# sensor-board.net
KiCad netlist of a schematic drawn in EAGLE
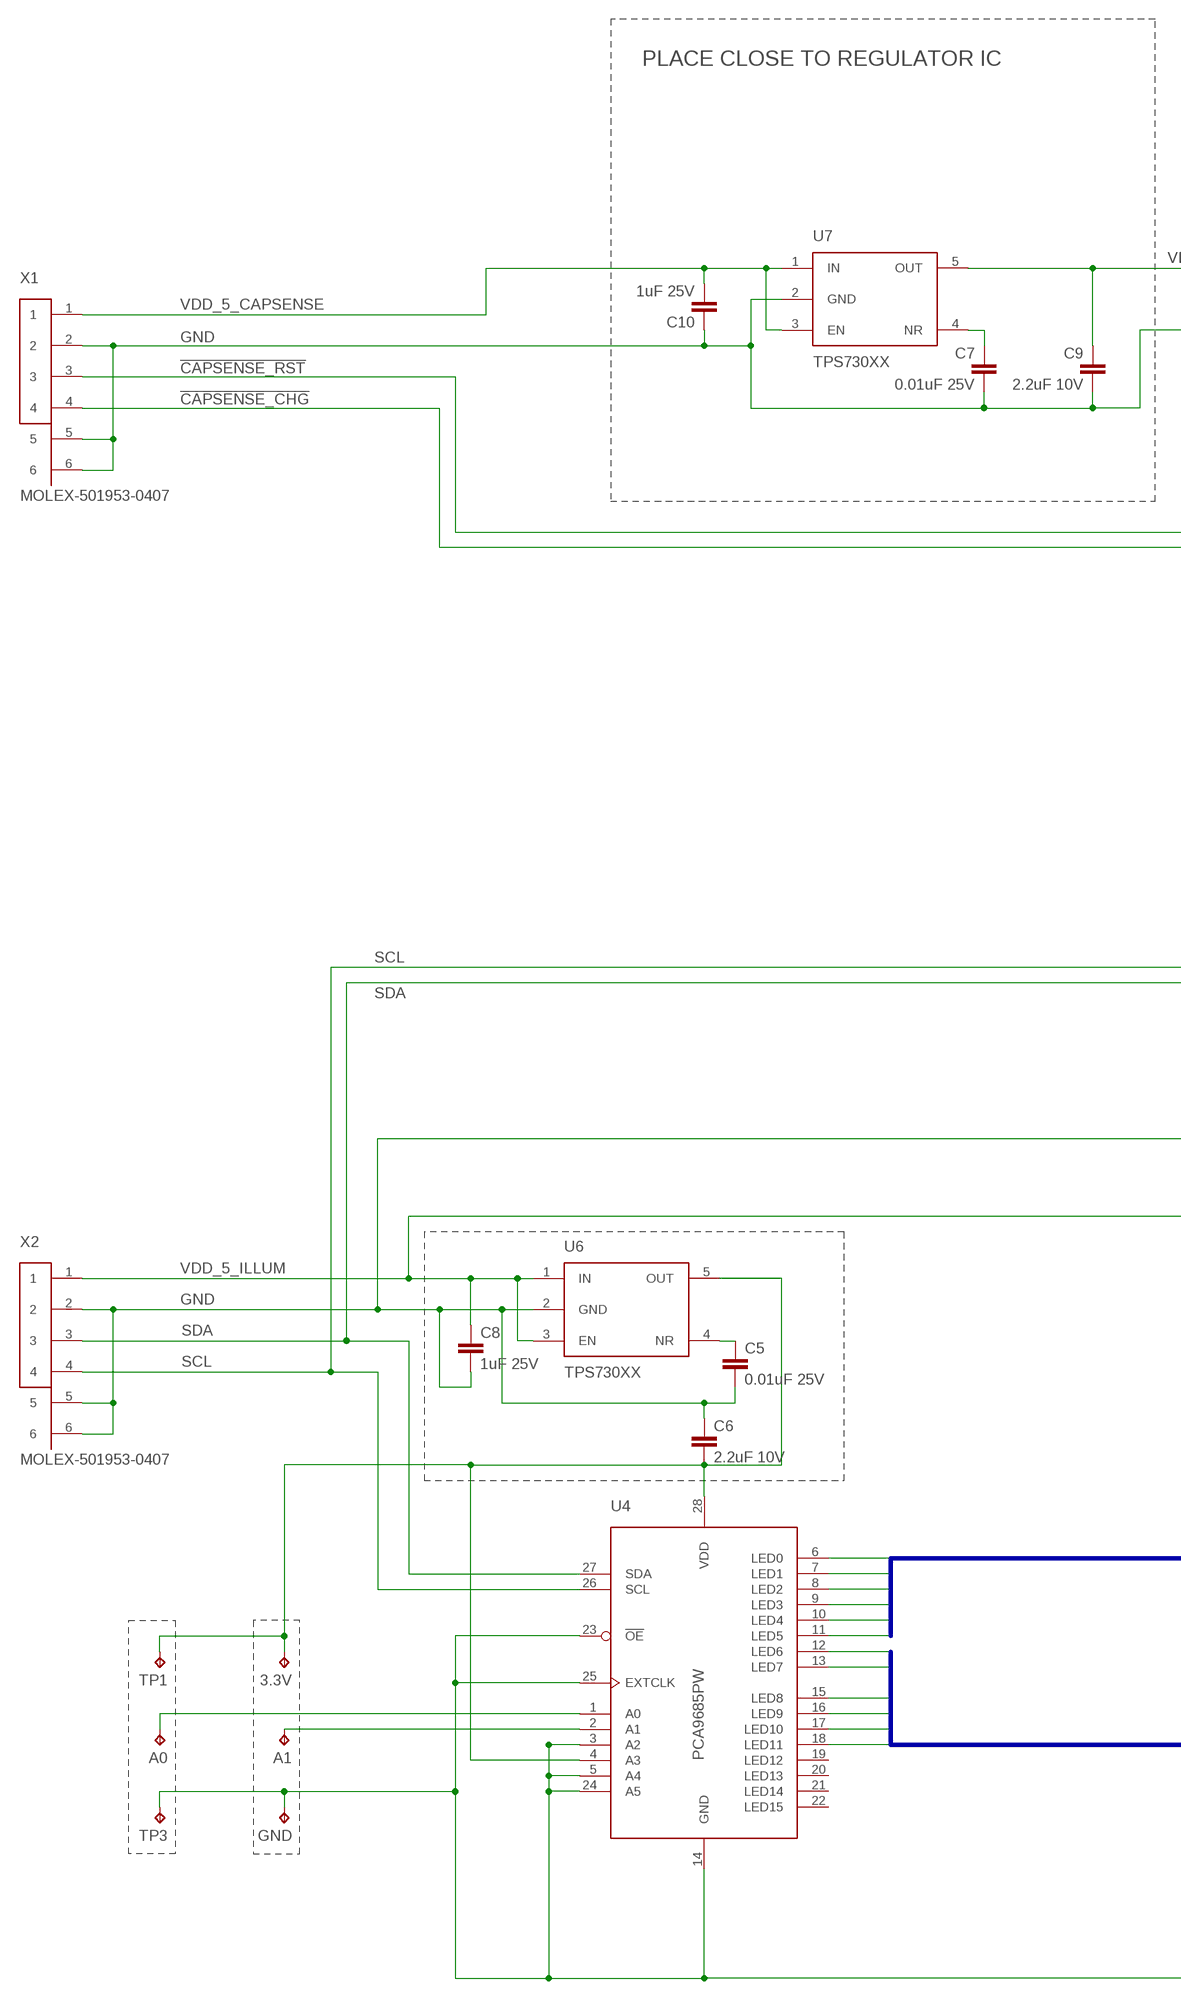
[diagram p0: schematic, sheet 1, part 1 of 2]
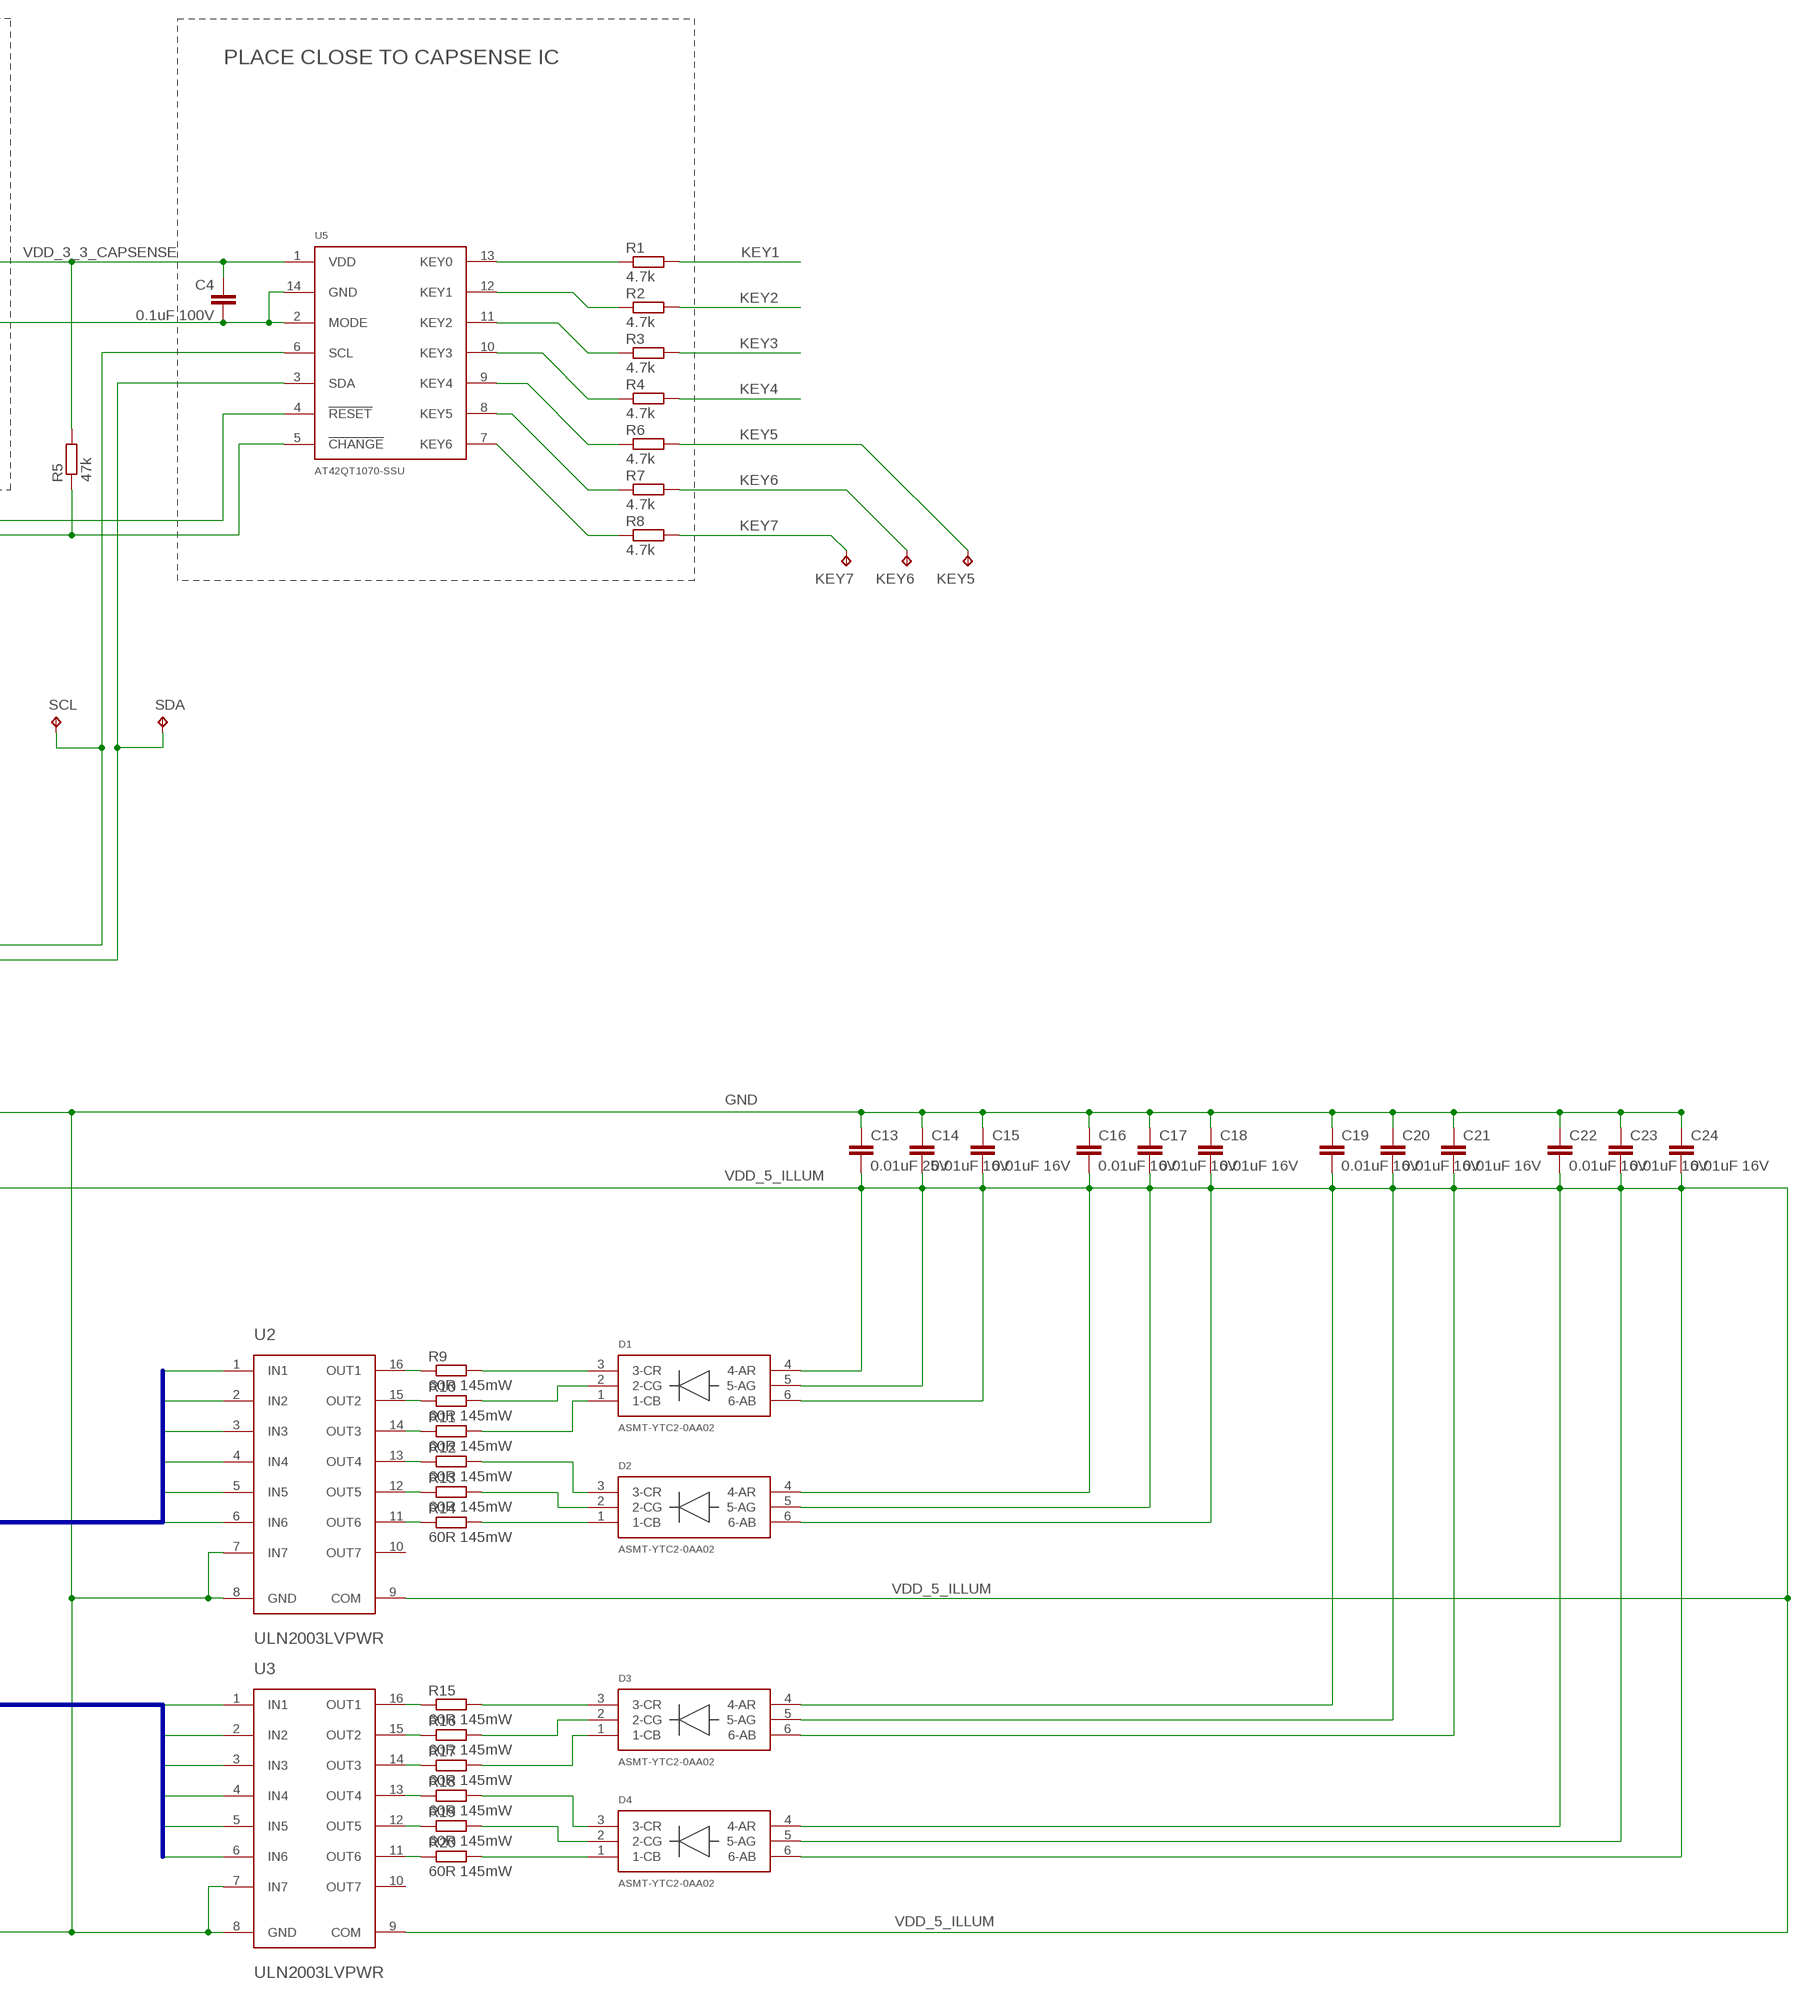
[diagram p1: schematic, sheet 1, part 2 of 2]

(export (version "E")
  (design (tool "Eeschema 10.0.6"))
  (components
    (comp (ref "3.3V")
      (value "TPB1,27")
      (footprint "eagle-import:B1,27")
      (libsource (lib "eagle-import") (part "TPB1,27"))
    )
    (comp (ref "A0")
      (value "TPB1,27")
      (footprint "eagle-import:B1,27")
      (libsource (lib "eagle-import") (part "TPB1,27"))
    )
    (comp (ref "A1")
      (value "TPB1,27")
      (footprint "eagle-import:B1,27")
      (libsource (lib "eagle-import") (part "TPB1,27"))
    )
    (comp (ref "C4")
      (value "0.1uF 100V")
      (footprint "eagle-import:C0402K")
      (fields (field (name "MFR_PART") "0402YC104KAT2A"))
      (libsource (lib "eagle-import") (part "C-EUC0402K"))
    )
    (comp (ref "C5")
      (value "0.01uF 25V")
      (footprint "eagle-import:C0402K")
      (fields (field (name "MFR_PART") "C0402C103J3RACTU"))
      (libsource (lib "eagle-import") (part "C-EUC0402K"))
    )
    (comp (ref "C6")
      (value "2.2uF 10V")
      (footprint "eagle-import:C0402K")
      (fields (field (name "MFR_PART") "C0402C225M8PAC TU "))
      (libsource (lib "eagle-import") (part "C-EUC0402K"))
    )
    (comp (ref "C7")
      (value "0.01uF 25V")
      (footprint "eagle-import:C0402K")
      (fields (field (name "MFR_PART") "C0402C103J3RACTU"))
      (libsource (lib "eagle-import") (part "C-EUC0402K"))
    )
    (comp (ref "C8")
      (value "1uF 25V")
      (footprint "eagle-import:C0402K")
      (fields (field (name "MFR_PART") "C1005X5R1A105K050BB"))
      (libsource (lib "eagle-import") (part "C-EUC0402K"))
    )
    (comp (ref "C9")
      (value "2.2uF 10V")
      (footprint "eagle-import:C0402K")
      (fields (field (name "MFR_PART") "C1608X7R1C105K080AC"))
      (libsource (lib "eagle-import") (part "C-EUC0402K"))
    )
    (comp (ref "C10")
      (value "1uF 25V")
      (footprint "eagle-import:C0402K")
      (fields (field (name "MFR_PART") "C1005X5R1A105K050BB"))
      (libsource (lib "eagle-import") (part "C-EUC0402K"))
    )
    (comp (ref "C13")
      (value "0.01uF 25V")
      (footprint "eagle-import:C0402K")
      (fields (field (name "MFR_PART") "C0402C103J3RACTU"))
      (libsource (lib "eagle-import") (part "C-EUC0402K"))
    )
    (comp (ref "C14")
      (value "0.01uF 16V")
      (footprint "eagle-import:C0402K")
      (fields (field (name "MFR_PART") "C0402C103J3RACTU"))
      (libsource (lib "eagle-import") (part "C-EUC0402K"))
    )
    (comp (ref "C15")
      (value "0.01uF 16V")
      (footprint "eagle-import:C0402K")
      (fields (field (name "MFR_PART") "C0402C103J3RACTU"))
      (libsource (lib "eagle-import") (part "C-EUC0402K"))
    )
    (comp (ref "C16")
      (value "0.01uF 16V")
      (footprint "eagle-import:C0402K")
      (fields (field (name "MFR_PART") "C0402C103J3RACTU"))
      (libsource (lib "eagle-import") (part "C-EUC0402K"))
    )
    (comp (ref "C17")
      (value "0.01uF 16V")
      (footprint "eagle-import:C0402K")
      (fields (field (name "MFR_PART") "C0402C103J3RACTU"))
      (libsource (lib "eagle-import") (part "C-EUC0402K"))
    )
    (comp (ref "C18")
      (value "0.01uF 16V")
      (footprint "eagle-import:C0402K")
      (fields (field (name "MFR_PART") "C0402C103J3RACTU"))
      (libsource (lib "eagle-import") (part "C-EUC0402K"))
    )
    (comp (ref "C19")
      (value "0.01uF 16V")
      (footprint "eagle-import:C0402K")
      (fields (field (name "MFR_PART") "C0402C103J3RACTU"))
      (libsource (lib "eagle-import") (part "C-EUC0402K"))
    )
    (comp (ref "C20")
      (value "0.01uF 16V")
      (footprint "eagle-import:C0402K")
      (fields (field (name "MFR_PART") "C0402C103J3RACTU"))
      (libsource (lib "eagle-import") (part "C-EUC0402K"))
    )
    (comp (ref "C21")
      (value "0.01uF 16V")
      (footprint "eagle-import:C0402K")
      (fields (field (name "MFR_PART") "C0402C103J3RACTU"))
      (libsource (lib "eagle-import") (part "C-EUC0402K"))
    )
    (comp (ref "C22")
      (value "0.01uF 16V")
      (footprint "eagle-import:C0402K")
      (fields (field (name "MFR_PART") "C0402C103J3RACTU"))
      (libsource (lib "eagle-import") (part "C-EUC0402K"))
    )
    (comp (ref "C23")
      (value "0.01uF 16V")
      (footprint "eagle-import:C0402K")
      (fields (field (name "MFR_PART") "C0402C103J3RACTU"))
      (libsource (lib "eagle-import") (part "C-EUC0402K"))
    )
    (comp (ref "C24")
      (value "0.01uF 16V")
      (footprint "eagle-import:C0402K")
      (fields (field (name "MFR_PART") "C0402C103J3RACTU"))
      (libsource (lib "eagle-import") (part "C-EUC0402K"))
    )
    (comp (ref "D1")
      (value "ASMT-YTC2-0AA02")
      (footprint "eagle-import:ASMT-YTC2-0AA02-REV")
      (libsource (lib "eagle-import") (part "ASMT-YTC2-0AA02"))
    )
    (comp (ref "D2")
      (value "ASMT-YTC2-0AA02")
      (footprint "eagle-import:ASMT-YTC2-0AA02-REV")
      (libsource (lib "eagle-import") (part "ASMT-YTC2-0AA02"))
    )
    (comp (ref "D3")
      (value "ASMT-YTC2-0AA02")
      (footprint "eagle-import:ASMT-YTC2-0AA02-REV")
      (libsource (lib "eagle-import") (part "ASMT-YTC2-0AA02"))
    )
    (comp (ref "D4")
      (value "ASMT-YTC2-0AA02")
      (footprint "eagle-import:ASMT-YTC2-0AA02-REV")
      (libsource (lib "eagle-import") (part "ASMT-YTC2-0AA02"))
    )
    (comp (ref "GND")
      (value "TPB1,27")
      (footprint "eagle-import:B1,27")
      (libsource (lib "eagle-import") (part "TPB1,27"))
    )
    (comp (ref "KEY5")
      (value "TPTP06R")
      (footprint "eagle-import:TP06R")
      (libsource (lib "eagle-import") (part "TPTP06R"))
    )
    (comp (ref "KEY6")
      (value "TPTP06R")
      (footprint "eagle-import:TP06R")
      (libsource (lib "eagle-import") (part "TPTP06R"))
    )
    (comp (ref "KEY7")
      (value "TPTP06R")
      (footprint "eagle-import:TP06R")
      (libsource (lib "eagle-import") (part "TPTP06R"))
    )
    (comp (ref "R1")
      (value "4.7k")
      (footprint "eagle-import:R0402")
      (fields (field (name "MFR_PART") "PCF0402PR-4K7BT1"))
      (libsource (lib "eagle-import") (part "R-EU_NKR0402"))
    )
    (comp (ref "R2")
      (value "4.7k")
      (footprint "eagle-import:R0402")
      (fields (field (name "MFR_PART") "PCF0402PR-4K7BT1 "))
      (libsource (lib "eagle-import") (part "R-EU_NKR0402"))
    )
    (comp (ref "R3")
      (value "4.7k")
      (footprint "eagle-import:R0402")
      (fields (field (name "MFR_PART") "PCF0402PR-4K7BT1 "))
      (libsource (lib "eagle-import") (part "R-EU_NKR0402"))
    )
    (comp (ref "R4")
      (value "4.7k")
      (footprint "eagle-import:R0402")
      (fields (field (name "MFR_PART") "PCF0402PR-4K7BT1 "))
      (libsource (lib "eagle-import") (part "R-EU_NKR0402"))
    )
    (comp (ref "R5")
      (value "47k")
      (footprint "eagle-import:R0402")
      (fields (field (name "MFR_PART") "RC0402JR-0747KL"))
      (libsource (lib "eagle-import") (part "R-EU_NKR0402"))
    )
    (comp (ref "R6")
      (value "4.7k")
      (footprint "eagle-import:R0402")
      (fields (field (name "MFR_PART") "PCF0402PR-4K7BT1 "))
      (libsource (lib "eagle-import") (part "R-EU_NKR0402"))
    )
    (comp (ref "R7")
      (value "4.7k")
      (footprint "eagle-import:R0402")
      (fields (field (name "MFR_PART") "PCF0402PR-4K7BT1 "))
      (libsource (lib "eagle-import") (part "R-EU_NKR0402"))
    )
    (comp (ref "R8")
      (value "4.7k")
      (footprint "eagle-import:R0402")
      (fields (field (name "MFR_PART") "PCF0402PR-4K7BT1 "))
      (libsource (lib "eagle-import") (part "R-EU_NKR0402"))
    )
    (comp (ref "R9")
      (value "60R 145mW")
      (footprint "eagle-import:R0603")
      (fields (field (name "MFR_PART") "ERJP03F62R0V"))
      (libsource (lib "eagle-import") (part "R-EU_NKR0603"))
    )
    (comp (ref "R10")
      (value "60R 145mW")
      (footprint "eagle-import:R0603")
      (fields (field (name "MFR_PART") "ERJP03F62R0V"))
      (libsource (lib "eagle-import") (part "R-EU_NKR0603"))
    )
    (comp (ref "R11")
      (value "60R 145mW")
      (footprint "eagle-import:R0603")
      (fields (field (name "MFR_PART") "ERJP03F62R0V"))
      (libsource (lib "eagle-import") (part "R-EU_NKR0603"))
    )
    (comp (ref "R12")
      (value "60R 145mW")
      (footprint "eagle-import:R0603")
      (fields (field (name "MFR_PART") "ERJP03F62R0V"))
      (libsource (lib "eagle-import") (part "R-EU_NKR0603"))
    )
    (comp (ref "R13")
      (value "60R 145mW")
      (footprint "eagle-import:R0603")
      (fields (field (name "MFR_PART") "ERJP03F62R0V"))
      (libsource (lib "eagle-import") (part "R-EU_NKR0603"))
    )
    (comp (ref "R14")
      (value "60R 145mW")
      (footprint "eagle-import:R0603")
      (fields (field (name "MFR_PART") "ERJP03F62R0V"))
      (libsource (lib "eagle-import") (part "R-EU_NKR0603"))
    )
    (comp (ref "R15")
      (value "60R 145mW")
      (footprint "eagle-import:R0603")
      (fields (field (name "MFR_PART") "ERJP03F62R0V"))
      (libsource (lib "eagle-import") (part "R-EU_NKR0603"))
    )
    (comp (ref "R16")
      (value "60R 145mW")
      (footprint "eagle-import:R0603")
      (fields (field (name "MFR_PART") "ERJP03F62R0V"))
      (libsource (lib "eagle-import") (part "R-EU_NKR0603"))
    )
    (comp (ref "R17")
      (value "60R 145mW")
      (footprint "eagle-import:R0603")
      (fields (field (name "MFR_PART") "ERJP03F62R0V"))
      (libsource (lib "eagle-import") (part "R-EU_NKR0603"))
    )
    (comp (ref "R18")
      (value "60R 145mW")
      (footprint "eagle-import:R0603")
      (fields (field (name "MFR_PART") "ERJP03F62R0V"))
      (libsource (lib "eagle-import") (part "R-EU_NKR0603"))
    )
    (comp (ref "R19")
      (value "60R 145mW")
      (footprint "eagle-import:R0603")
      (fields (field (name "MFR_PART") "ERJP03F62R0V"))
      (libsource (lib "eagle-import") (part "R-EU_NKR0603"))
    )
    (comp (ref "R20")
      (value "60R 145mW")
      (footprint "eagle-import:R0603")
      (fields (field (name "MFR_PART") "ERJP03F62R0V"))
      (libsource (lib "eagle-import") (part "R-EU_NKR0603"))
    )
    (comp (ref "SCL")
      (value "TPTP06R")
      (footprint "eagle-import:TP06R")
      (libsource (lib "eagle-import") (part "TPTP06R"))
    )
    (comp (ref "SDA")
      (value "TPTP06R")
      (footprint "eagle-import:TP06R")
      (libsource (lib "eagle-import") (part "TPTP06R"))
    )
    (comp (ref "TP1")
      (value "TPB1,27")
      (footprint "eagle-import:B1,27")
      (libsource (lib "eagle-import") (part "TPB1,27"))
    )
    (comp (ref "TP3")
      (value "TPB1,27")
      (footprint "eagle-import:B1,27")
      (libsource (lib "eagle-import") (part "TPB1,27"))
    )
    (comp (ref "U2")
      (value "ULN2003LVPWR")
      (footprint "eagle-import:TSSOP-PW-R-PDSO-G16")
      (libsource (lib "eagle-import") (part "ULN2003LVPWR"))
    )
    (comp (ref "U3")
      (value "ULN2003LVPWR")
      (footprint "eagle-import:TSSOP-PW-R-PDSO-G16")
      (libsource (lib "eagle-import") (part "ULN2003LVPWR"))
    )
    (comp (ref "U4")
      (value "PCA9685PW")
      (footprint "eagle-import:SOT361-1")
      (libsource (lib "eagle-import") (part "PCA9685PW"))
    )
    (comp (ref "U5")
      (value "AT42QT1070-SSU")
      (footprint "eagle-import:SO14")
      (libsource (lib "eagle-import") (part "AT42QT1070-SSU"))
    )
    (comp (ref "U6")
      (value "TPS730XX")
      (footprint "eagle-import:SOT23-5")
      (libsource (lib "eagle-import") (part "TPS730XX"))
    )
    (comp (ref "U7")
      (value "TPS730XX")
      (footprint "eagle-import:SOT23-5")
      (libsource (lib "eagle-import") (part "TPS730XX"))
    )
    (comp (ref "X1")
      (value "MOLEX-501953-0407")
      (footprint "eagle-import:MOLEX-501953-0407")
      (libsource (lib "eagle-import") (part "MOLEX-501953-0407"))
    )
    (comp (ref "X2")
      (value "MOLEX-501953-0407")
      (footprint "eagle-import:MOLEX-501953-0407")
      (libsource (lib "eagle-import") (part "MOLEX-501953-0407"))
    )
  )
  (nets
    (net (code "1") (name "/GND") (class "Default")
      (node (ref "C10") (pin "1") (pinfunction "1_1") (pintype "passive"))
      (node (ref "C13") (pin "1") (pinfunction "1_1") (pintype "passive"))
      (node (ref "C14") (pin "1") (pinfunction "1_1") (pintype "passive"))
      (node (ref "C15") (pin "1") (pinfunction "1_1") (pintype "passive"))
      (node (ref "C16") (pin "1") (pinfunction "1_1") (pintype "passive"))
      (node (ref "C17") (pin "1") (pinfunction "1_1") (pintype "passive"))
      (node (ref "C18") (pin "1") (pinfunction "1_1") (pintype "passive"))
      (node (ref "C19") (pin "1") (pinfunction "1_1") (pintype "passive"))
      (node (ref "C20") (pin "1") (pinfunction "1_1") (pintype "passive"))
      (node (ref "C21") (pin "1") (pinfunction "1_1") (pintype "passive"))
      (node (ref "C22") (pin "1") (pinfunction "1_1") (pintype "passive"))
      (node (ref "C23") (pin "1") (pinfunction "1_1") (pintype "passive"))
      (node (ref "C24") (pin "1") (pinfunction "1_1") (pintype "passive"))
      (node (ref "C4") (pin "2") (pinfunction "2_2") (pintype "passive"))
      (node (ref "C5") (pin "2") (pinfunction "2_2") (pintype "passive"))
      (node (ref "C6") (pin "1") (pinfunction "1_1") (pintype "passive"))
      (node (ref "C7") (pin "2") (pinfunction "2_2") (pintype "passive"))
      (node (ref "C8") (pin "2") (pinfunction "2_2") (pintype "passive"))
      (node (ref "C9") (pin "2") (pinfunction "2_2") (pintype "passive"))
      (node (ref "GND") (pin "TP") (pinfunction "TP_TP") (pintype "input"))
      (node (ref "TP3") (pin "TP") (pinfunction "TP_TP") (pintype "input"))
      (node (ref "U2") (pin "7") (pinfunction "IN7_7") (pintype "bidirectional"))
      (node (ref "U2") (pin "8") (pinfunction "GND_8") (pintype "power_in"))
      (node (ref "U3") (pin "7") (pinfunction "IN7_7") (pintype "bidirectional"))
      (node (ref "U3") (pin "8") (pinfunction "GND_8") (pintype "power_in"))
      (node (ref "U4") (pin "14") (pinfunction "GND_14") (pintype "power_in"))
      (node (ref "U4") (pin "23") (pinfunction "~{OE}_23") (pintype "bidirectional"))
      (node (ref "U4") (pin "24") (pinfunction "A5_24") (pintype "bidirectional"))
      (node (ref "U4") (pin "25") (pinfunction "EXTCLK_25") (pintype "input"))
      (node (ref "U4") (pin "3") (pinfunction "A2_3") (pintype "bidirectional"))
      (node (ref "U4") (pin "5") (pinfunction "A4_5") (pintype "bidirectional"))
      (node (ref "U5") (pin "14") (pinfunction "GND_14") (pintype "power_in"))
      (node (ref "U5") (pin "2") (pinfunction "MODE_2") (pintype "input"))
      (node (ref "U6") (pin "2") (pinfunction "GND_2") (pintype "power_in"))
      (node (ref "U7") (pin "2") (pinfunction "GND_2") (pintype "power_in"))
      (node (ref "X1") (pin "2") (pinfunction "2_2") (pintype "bidirectional"))
      (node (ref "X1") (pin "5") (pinfunction "5_5") (pintype "bidirectional"))
      (node (ref "X1") (pin "6") (pinfunction "6_6") (pintype "bidirectional"))
      (node (ref "X2") (pin "2") (pinfunction "2_2") (pintype "bidirectional"))
      (node (ref "X2") (pin "5") (pinfunction "5_5") (pintype "bidirectional"))
      (node (ref "X2") (pin "6") (pinfunction "6_6") (pintype "bidirectional"))
    )
    (net (code "2") (name "/KEY1") (class "Default")
      (node (ref "R1") (pin "2") (pinfunction "2_2") (pintype "passive"))
    )
    (net (code "3") (name "/KEY2") (class "Default")
      (node (ref "R2") (pin "2") (pinfunction "2_2") (pintype "passive"))
    )
    (net (code "4") (name "/KEY3") (class "Default")
      (node (ref "R3") (pin "2") (pinfunction "2_2") (pintype "passive"))
    )
    (net (code "5") (name "/KEY4") (class "Default")
      (node (ref "R4") (pin "2") (pinfunction "2_2") (pintype "passive"))
    )
    (net (code "6") (name "/KEY5") (class "Default")
      (node (ref "KEY5") (pin "TP") (pinfunction "TP_TP") (pintype "input"))
      (node (ref "R6") (pin "2") (pinfunction "2_2") (pintype "passive"))
    )
    (net (code "7") (name "/KEY6") (class "Default")
      (node (ref "KEY6") (pin "TP") (pinfunction "TP_TP") (pintype "input"))
      (node (ref "R7") (pin "2") (pinfunction "2_2") (pintype "passive"))
    )
    (net (code "8") (name "/KEY7") (class "Default")
      (node (ref "KEY7") (pin "TP") (pinfunction "TP_TP") (pintype "input"))
      (node (ref "R8") (pin "2") (pinfunction "2_2") (pintype "passive"))
    )
    (net (code "9") (name "/LEDOUT_A1") (class "Default")
      (node (ref "U2") (pin "1") (pinfunction "IN1_1") (pintype "bidirectional"))
      (node (ref "U4") (pin "6") (pinfunction "LED0_6") (pintype "bidirectional"))
    )
    (net (code "10") (name "/LEDOUT_A2") (class "Default")
      (node (ref "U2") (pin "2") (pinfunction "IN2_2") (pintype "bidirectional"))
      (node (ref "U4") (pin "7") (pinfunction "LED1_7") (pintype "bidirectional"))
    )
    (net (code "11") (name "/LEDOUT_A3") (class "Default")
      (node (ref "U2") (pin "3") (pinfunction "IN3_3") (pintype "bidirectional"))
      (node (ref "U4") (pin "8") (pinfunction "LED2_8") (pintype "bidirectional"))
    )
    (net (code "12") (name "/LEDOUT_A4") (class "Default")
      (node (ref "U2") (pin "4") (pinfunction "IN4_4") (pintype "bidirectional"))
      (node (ref "U4") (pin "9") (pinfunction "LED3_9") (pintype "bidirectional"))
    )
    (net (code "13") (name "/LEDOUT_A5") (class "Default")
      (node (ref "U2") (pin "5") (pinfunction "IN5_5") (pintype "bidirectional"))
      (node (ref "U4") (pin "10") (pinfunction "LED4_10") (pintype "bidirectional"))
    )
    (net (code "14") (name "/LEDOUT_A6") (class "Default")
      (node (ref "U2") (pin "6") (pinfunction "IN6_6") (pintype "bidirectional"))
      (node (ref "U4") (pin "11") (pinfunction "LED5_11") (pintype "bidirectional"))
    )
    (net (code "15") (name "/LEDOUT_B1") (class "Default")
      (node (ref "U3") (pin "1") (pinfunction "IN1_1") (pintype "bidirectional"))
      (node (ref "U4") (pin "12") (pinfunction "LED6_12") (pintype "bidirectional"))
    )
    (net (code "16") (name "/LEDOUT_B2") (class "Default")
      (node (ref "U3") (pin "2") (pinfunction "IN2_2") (pintype "bidirectional"))
      (node (ref "U4") (pin "13") (pinfunction "LED7_13") (pintype "bidirectional"))
    )
    (net (code "17") (name "/LEDOUT_B3") (class "Default")
      (node (ref "U3") (pin "3") (pinfunction "IN3_3") (pintype "bidirectional"))
      (node (ref "U4") (pin "15") (pinfunction "LED8_15") (pintype "bidirectional"))
    )
    (net (code "18") (name "/LEDOUT_B4") (class "Default")
      (node (ref "U3") (pin "4") (pinfunction "IN4_4") (pintype "bidirectional"))
      (node (ref "U4") (pin "16") (pinfunction "LED9_16") (pintype "bidirectional"))
    )
    (net (code "19") (name "/LEDOUT_B5") (class "Default")
      (node (ref "U3") (pin "5") (pinfunction "IN5_5") (pintype "bidirectional"))
      (node (ref "U4") (pin "17") (pinfunction "LED10_17") (pintype "bidirectional"))
    )
    (net (code "20") (name "/LEDOUT_B6") (class "Default")
      (node (ref "U3") (pin "6") (pinfunction "IN6_6") (pintype "bidirectional"))
      (node (ref "U4") (pin "18") (pinfunction "LED11_18") (pintype "bidirectional"))
    )
    (net (code "21") (name "/SCL") (class "Default")
      (node (ref "SCL") (pin "TP") (pinfunction "TP_TP") (pintype "input"))
      (node (ref "U4") (pin "26") (pinfunction "SCL_26") (pintype "open_collector"))
      (node (ref "U5") (pin "6") (pinfunction "SCL_6") (pintype "open_collector"))
      (node (ref "X2") (pin "4") (pinfunction "4_4") (pintype "bidirectional"))
    )
    (net (code "22") (name "/SDA") (class "Default")
      (node (ref "SDA") (pin "TP") (pinfunction "TP_TP") (pintype "input"))
      (node (ref "U4") (pin "27") (pinfunction "SDA_27") (pintype "open_collector"))
      (node (ref "U5") (pin "3") (pinfunction "SDA_3") (pintype "open_collector"))
      (node (ref "X2") (pin "3") (pinfunction "3_3") (pintype "bidirectional"))
    )
    (net (code "23") (name "/VDD_3_3_CAPSENSE") (class "Default")
      (node (ref "C4") (pin "1") (pinfunction "1_1") (pintype "passive"))
      (node (ref "C9") (pin "1") (pinfunction "1_1") (pintype "passive"))
      (node (ref "R5") (pin "2") (pinfunction "2_2") (pintype "passive"))
      (node (ref "U5") (pin "1") (pinfunction "VDD_1") (pintype "power_in"))
      (node (ref "U7") (pin "5") (pinfunction "OUT_5") (pintype "power_in"))
    )
    (net (code "24") (name "/VDD_5_CAPSENSE") (class "Default")
      (node (ref "C10") (pin "2") (pinfunction "2_2") (pintype "passive"))
      (node (ref "U7") (pin "1") (pinfunction "IN_1") (pintype "power_in"))
      (node (ref "U7") (pin "3") (pinfunction "EN_3") (pintype "bidirectional"))
      (node (ref "X1") (pin "1") (pinfunction "1_1") (pintype "bidirectional"))
    )
    (net (code "25") (name "/VDD_5_ILLUM") (class "Default")
      (node (ref "C13") (pin "2") (pinfunction "2_2") (pintype "passive"))
      (node (ref "C14") (pin "2") (pinfunction "2_2") (pintype "passive"))
      (node (ref "C15") (pin "2") (pinfunction "2_2") (pintype "passive"))
      (node (ref "C16") (pin "2") (pinfunction "2_2") (pintype "passive"))
      (node (ref "C17") (pin "2") (pinfunction "2_2") (pintype "passive"))
      (node (ref "C18") (pin "2") (pinfunction "2_2") (pintype "passive"))
      (node (ref "C19") (pin "2") (pinfunction "2_2") (pintype "passive"))
      (node (ref "C20") (pin "2") (pinfunction "2_2") (pintype "passive"))
      (node (ref "C21") (pin "2") (pinfunction "2_2") (pintype "passive"))
      (node (ref "C22") (pin "2") (pinfunction "2_2") (pintype "passive"))
      (node (ref "C23") (pin "2") (pinfunction "2_2") (pintype "passive"))
      (node (ref "C24") (pin "2") (pinfunction "2_2") (pintype "passive"))
      (node (ref "C8") (pin "1") (pinfunction "1_1") (pintype "passive"))
      (node (ref "D1") (pin "4") (pinfunction "4-AR_4") (pintype "bidirectional"))
      (node (ref "D1") (pin "5") (pinfunction "5-AG_5") (pintype "bidirectional"))
      (node (ref "D1") (pin "6") (pinfunction "6-AB_6") (pintype "bidirectional"))
      (node (ref "D2") (pin "4") (pinfunction "4-AR_4") (pintype "bidirectional"))
      (node (ref "D2") (pin "5") (pinfunction "5-AG_5") (pintype "bidirectional"))
      (node (ref "D2") (pin "6") (pinfunction "6-AB_6") (pintype "bidirectional"))
      (node (ref "D3") (pin "4") (pinfunction "4-AR_4") (pintype "bidirectional"))
      (node (ref "D3") (pin "5") (pinfunction "5-AG_5") (pintype "bidirectional"))
      (node (ref "D3") (pin "6") (pinfunction "6-AB_6") (pintype "bidirectional"))
      (node (ref "D4") (pin "4") (pinfunction "4-AR_4") (pintype "bidirectional"))
      (node (ref "D4") (pin "5") (pinfunction "5-AG_5") (pintype "bidirectional"))
      (node (ref "D4") (pin "6") (pinfunction "6-AB_6") (pintype "bidirectional"))
      (node (ref "U2") (pin "9") (pinfunction "COM_9") (pintype "bidirectional"))
      (node (ref "U3") (pin "9") (pinfunction "COM_9") (pintype "bidirectional"))
      (node (ref "U6") (pin "1") (pinfunction "IN_1") (pintype "power_in"))
      (node (ref "U6") (pin "3") (pinfunction "EN_3") (pintype "bidirectional"))
      (node (ref "X2") (pin "1") (pinfunction "1_1") (pintype "bidirectional"))
    )
    (net (code "26") (name "/~{CAPSENSE_CHG}") (class "Default")
      (node (ref "R5") (pin "1") (pinfunction "1_1") (pintype "passive"))
      (node (ref "U5") (pin "5") (pinfunction "~{CHANGE}_5") (pintype "output"))
      (node (ref "X1") (pin "4") (pinfunction "4_4") (pintype "bidirectional"))
    )
    (net (code "27") (name "/~{CAPSENSE_RST}") (class "Default")
      (node (ref "U5") (pin "4") (pinfunction "~{RESET}_4") (pintype "input"))
      (node (ref "X1") (pin "3") (pinfunction "3_3") (pintype "bidirectional"))
    )
    (net (code "28") (name "Net-(D1-1-CB)") (class "Default")
      (node (ref "D1") (pin "1") (pinfunction "1-CB_1") (pintype "bidirectional"))
      (node (ref "R11") (pin "2") (pinfunction "2_2") (pintype "passive"))
    )
    (net (code "29") (name "Net-(D1-2-CG)") (class "Default")
      (node (ref "D1") (pin "2") (pinfunction "2-CG_2") (pintype "bidirectional"))
      (node (ref "R10") (pin "2") (pinfunction "2_2") (pintype "passive"))
    )
    (net (code "30") (name "Net-(D1-3-CR)") (class "Default")
      (node (ref "D1") (pin "3") (pinfunction "3-CR_3") (pintype "bidirectional"))
      (node (ref "R9") (pin "2") (pinfunction "2_2") (pintype "passive"))
    )
    (net (code "31") (name "Net-(D2-1-CB)") (class "Default")
      (node (ref "D2") (pin "1") (pinfunction "1-CB_1") (pintype "bidirectional"))
      (node (ref "R14") (pin "2") (pinfunction "2_2") (pintype "passive"))
    )
    (net (code "32") (name "Net-(D2-2-CG)") (class "Default")
      (node (ref "D2") (pin "2") (pinfunction "2-CG_2") (pintype "bidirectional"))
      (node (ref "R13") (pin "2") (pinfunction "2_2") (pintype "passive"))
    )
    (net (code "33") (name "Net-(D2-3-CR)") (class "Default")
      (node (ref "D2") (pin "3") (pinfunction "3-CR_3") (pintype "bidirectional"))
      (node (ref "R12") (pin "2") (pinfunction "2_2") (pintype "passive"))
    )
    (net (code "34") (name "Net-(D3-1-CB)") (class "Default")
      (node (ref "D3") (pin "1") (pinfunction "1-CB_1") (pintype "bidirectional"))
      (node (ref "R17") (pin "2") (pinfunction "2_2") (pintype "passive"))
    )
    (net (code "35") (name "Net-(D3-2-CG)") (class "Default")
      (node (ref "D3") (pin "2") (pinfunction "2-CG_2") (pintype "bidirectional"))
      (node (ref "R16") (pin "2") (pinfunction "2_2") (pintype "passive"))
    )
    (net (code "36") (name "Net-(D3-3-CR)") (class "Default")
      (node (ref "D3") (pin "3") (pinfunction "3-CR_3") (pintype "bidirectional"))
      (node (ref "R15") (pin "2") (pinfunction "2_2") (pintype "passive"))
    )
    (net (code "37") (name "Net-(D4-1-CB)") (class "Default")
      (node (ref "D4") (pin "1") (pinfunction "1-CB_1") (pintype "bidirectional"))
      (node (ref "R20") (pin "2") (pinfunction "2_2") (pintype "passive"))
    )
    (net (code "38") (name "Net-(D4-2-CG)") (class "Default")
      (node (ref "D4") (pin "2") (pinfunction "2-CG_2") (pintype "bidirectional"))
      (node (ref "R19") (pin "2") (pinfunction "2_2") (pintype "passive"))
    )
    (net (code "39") (name "Net-(D4-3-CR)") (class "Default")
      (node (ref "D4") (pin "3") (pinfunction "3-CR_3") (pintype "bidirectional"))
      (node (ref "R18") (pin "2") (pinfunction "2_2") (pintype "passive"))
    )
    (net (code "40") (name "Net-(U2-OUT1)") (class "Default")
      (node (ref "R9") (pin "1") (pinfunction "1_1") (pintype "passive"))
      (node (ref "U2") (pin "16") (pinfunction "OUT1_16") (pintype "bidirectional"))
    )
    (net (code "41") (name "Net-(U2-OUT2)") (class "Default")
      (node (ref "R10") (pin "1") (pinfunction "1_1") (pintype "passive"))
      (node (ref "U2") (pin "15") (pinfunction "OUT2_15") (pintype "bidirectional"))
    )
    (net (code "42") (name "Net-(U2-OUT3)") (class "Default")
      (node (ref "R11") (pin "1") (pinfunction "1_1") (pintype "passive"))
      (node (ref "U2") (pin "14") (pinfunction "OUT3_14") (pintype "bidirectional"))
    )
    (net (code "43") (name "Net-(U2-OUT4)") (class "Default")
      (node (ref "R12") (pin "1") (pinfunction "1_1") (pintype "passive"))
      (node (ref "U2") (pin "13") (pinfunction "OUT4_13") (pintype "bidirectional"))
    )
    (net (code "44") (name "Net-(U2-OUT5)") (class "Default")
      (node (ref "R13") (pin "1") (pinfunction "1_1") (pintype "passive"))
      (node (ref "U2") (pin "12") (pinfunction "OUT5_12") (pintype "bidirectional"))
    )
    (net (code "45") (name "Net-(U2-OUT6)") (class "Default")
      (node (ref "R14") (pin "1") (pinfunction "1_1") (pintype "passive"))
      (node (ref "U2") (pin "11") (pinfunction "OUT6_11") (pintype "bidirectional"))
    )
    (net (code "46") (name "Net-(U3-OUT1)") (class "Default")
      (node (ref "R15") (pin "1") (pinfunction "1_1") (pintype "passive"))
      (node (ref "U3") (pin "16") (pinfunction "OUT1_16") (pintype "bidirectional"))
    )
    (net (code "47") (name "Net-(U3-OUT2)") (class "Default")
      (node (ref "R16") (pin "1") (pinfunction "1_1") (pintype "passive"))
      (node (ref "U3") (pin "15") (pinfunction "OUT2_15") (pintype "bidirectional"))
    )
    (net (code "48") (name "Net-(U3-OUT3)") (class "Default")
      (node (ref "R17") (pin "1") (pinfunction "1_1") (pintype "passive"))
      (node (ref "U3") (pin "14") (pinfunction "OUT3_14") (pintype "bidirectional"))
    )
    (net (code "49") (name "Net-(U3-OUT4)") (class "Default")
      (node (ref "R18") (pin "1") (pinfunction "1_1") (pintype "passive"))
      (node (ref "U3") (pin "13") (pinfunction "OUT4_13") (pintype "bidirectional"))
    )
    (net (code "50") (name "Net-(U3-OUT5)") (class "Default")
      (node (ref "R19") (pin "1") (pinfunction "1_1") (pintype "passive"))
      (node (ref "U3") (pin "12") (pinfunction "OUT5_12") (pintype "bidirectional"))
    )
    (net (code "51") (name "Net-(U3-OUT6)") (class "Default")
      (node (ref "R20") (pin "1") (pinfunction "1_1") (pintype "passive"))
      (node (ref "U3") (pin "11") (pinfunction "OUT6_11") (pintype "bidirectional"))
    )
    (net (code "52") (name "Net-(U4-A0)") (class "Default")
      (node (ref "A0") (pin "TP") (pinfunction "TP_TP") (pintype "input"))
      (node (ref "U4") (pin "1") (pinfunction "A0_1") (pintype "bidirectional"))
    )
    (net (code "53") (name "Net-(U4-A1)") (class "Default")
      (node (ref "A1") (pin "TP") (pinfunction "TP_TP") (pintype "input"))
      (node (ref "U4") (pin "2") (pinfunction "A1_2") (pintype "bidirectional"))
    )
    (net (code "54") (name "Net-(U4-A3)") (class "Default")
      (node (ref "3.3V") (pin "TP") (pinfunction "TP_TP") (pintype "input"))
      (node (ref "C6") (pin "2") (pinfunction "2_2") (pintype "passive"))
      (node (ref "TP1") (pin "TP") (pinfunction "TP_TP") (pintype "input"))
      (node (ref "U4") (pin "28") (pinfunction "VDD_28") (pintype "power_in"))
      (node (ref "U4") (pin "4") (pinfunction "A3_4") (pintype "bidirectional"))
      (node (ref "U6") (pin "5") (pinfunction "OUT_5") (pintype "power_in"))
    )
    (net (code "55") (name "Net-(U5-KEY0)") (class "Default")
      (node (ref "R1") (pin "1") (pinfunction "1_1") (pintype "passive"))
      (node (ref "U5") (pin "13") (pinfunction "KEY0_13") (pintype "output"))
    )
    (net (code "56") (name "Net-(U5-KEY1)") (class "Default")
      (node (ref "R2") (pin "1") (pinfunction "1_1") (pintype "passive"))
      (node (ref "U5") (pin "12") (pinfunction "KEY1_12") (pintype "output"))
    )
    (net (code "57") (name "Net-(U5-KEY2)") (class "Default")
      (node (ref "R3") (pin "1") (pinfunction "1_1") (pintype "passive"))
      (node (ref "U5") (pin "11") (pinfunction "KEY2_11") (pintype "output"))
    )
    (net (code "58") (name "Net-(U5-KEY3)") (class "Default")
      (node (ref "R4") (pin "1") (pinfunction "1_1") (pintype "passive"))
      (node (ref "U5") (pin "10") (pinfunction "KEY3_10") (pintype "output"))
    )
    (net (code "59") (name "Net-(U5-KEY4)") (class "Default")
      (node (ref "R6") (pin "1") (pinfunction "1_1") (pintype "passive"))
      (node (ref "U5") (pin "9") (pinfunction "KEY4_9") (pintype "output"))
    )
    (net (code "60") (name "Net-(U5-KEY5)") (class "Default")
      (node (ref "R7") (pin "1") (pinfunction "1_1") (pintype "passive"))
      (node (ref "U5") (pin "8") (pinfunction "KEY5_8") (pintype "output"))
    )
    (net (code "61") (name "Net-(U5-KEY6)") (class "Default")
      (node (ref "R8") (pin "1") (pinfunction "1_1") (pintype "passive"))
      (node (ref "U5") (pin "7") (pinfunction "KEY6_7") (pintype "output"))
    )
    (net (code "62") (name "Net-(U6-NR)") (class "Default")
      (node (ref "C5") (pin "1") (pinfunction "1_1") (pintype "passive"))
      (node (ref "U6") (pin "4") (pinfunction "NR_4") (pintype "bidirectional"))
    )
    (net (code "63") (name "Net-(U7-NR)") (class "Default")
      (node (ref "C7") (pin "1") (pinfunction "1_1") (pintype "passive"))
      (node (ref "U7") (pin "4") (pinfunction "NR_4") (pintype "bidirectional"))
    )
    (net (code "64") (name "unconnected-(U2-OUT7-Pad10)") (class "Default")
      (node (ref "U2") (pin "10") (pinfunction "OUT7_10") (pintype "bidirectional"))
    )
    (net (code "65") (name "unconnected-(U3-OUT7-Pad10)") (class "Default")
      (node (ref "U3") (pin "10") (pinfunction "OUT7_10") (pintype "bidirectional"))
    )
    (net (code "66") (name "unconnected-(U4-LED12-Pad19)") (class "Default")
      (node (ref "U4") (pin "19") (pinfunction "LED12_19") (pintype "bidirectional"))
    )
    (net (code "67") (name "unconnected-(U4-LED13-Pad20)") (class "Default")
      (node (ref "U4") (pin "20") (pinfunction "LED13_20") (pintype "bidirectional"))
    )
    (net (code "68") (name "unconnected-(U4-LED14-Pad21)") (class "Default")
      (node (ref "U4") (pin "21") (pinfunction "LED14_21") (pintype "bidirectional"))
    )
    (net (code "69") (name "unconnected-(U4-LED15-Pad22)") (class "Default")
      (node (ref "U4") (pin "22") (pinfunction "LED15_22") (pintype "bidirectional"))
    )
  )
)
